# SPI_Encoders.net
KiCad netlist of a schematic drawn in Altium Designer
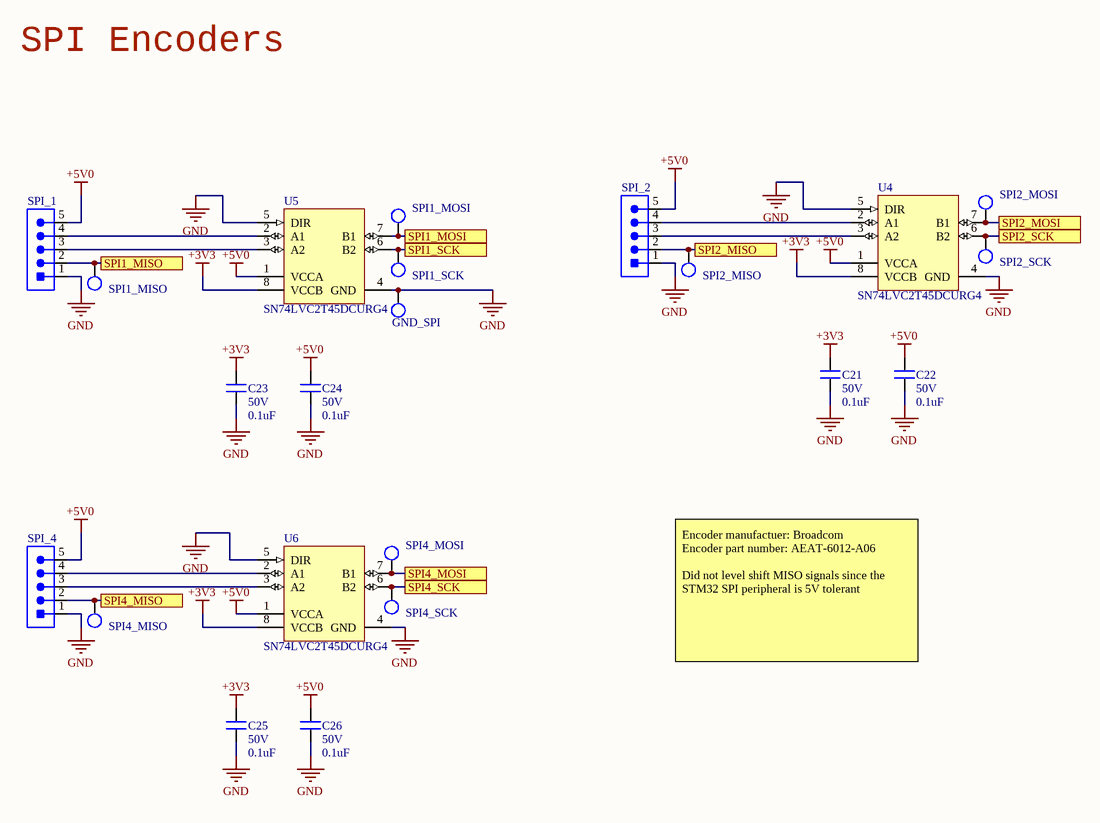
[diagram p0: SPI Encoders.SchDoc]

(export (version "E")
  (design (tool "Eeschema 10.0.6"))
  (components
    (comp (ref "C21")
      (value "0.1uF")
      (footprint "CAPC0603(1608)55_N")
      (description "CAP CER 0.1UF 50V X7R 0603")
      (fields
        (field (name "MPN") "CC0603KRX7R9BB104")
        (field (name "MANUFACTURER") "Yageo")
        (field (name "VOLTAGE RATING") "50V")
      )
      (libsource (lib "UWRT_Schematic_Library_2020") (part "CAP_0.1uF_50V_0603"))
    )
    (comp (ref "C22")
      (value "0.1uF")
      (footprint "CAPC0603(1608)55_N")
      (description "CAP CER 0.1UF 50V X7R 0603")
      (fields
        (field (name "MPN") "CC0603KRX7R9BB104")
        (field (name "MANUFACTURER") "Yageo")
        (field (name "VOLTAGE RATING") "50V")
      )
      (libsource (lib "UWRT_Schematic_Library_2020") (part "CAP_0.1uF_50V_0603"))
    )
    (comp (ref "C23")
      (value "0.1uF")
      (footprint "CAPC0603(1608)55_N")
      (description "CAP CER 0.1UF 50V X7R 0603")
      (fields
        (field (name "MPN") "CC0603KRX7R9BB104")
        (field (name "MANUFACTURER") "Yageo")
        (field (name "VOLTAGE RATING") "50V")
      )
      (libsource (lib "UWRT_Schematic_Library_2020") (part "CAP_0.1uF_50V_0603"))
    )
    (comp (ref "C24")
      (value "0.1uF")
      (footprint "CAPC0603(1608)55_N")
      (description "CAP CER 0.1UF 50V X7R 0603")
      (fields
        (field (name "MPN") "CC0603KRX7R9BB104")
        (field (name "MANUFACTURER") "Yageo")
        (field (name "VOLTAGE RATING") "50V")
      )
      (libsource (lib "UWRT_Schematic_Library_2020") (part "CAP_0.1uF_50V_0603"))
    )
    (comp (ref "C25")
      (value "0.1uF")
      (footprint "CAPC0603(1608)55_N")
      (description "CAP CER 0.1UF 50V X7R 0603")
      (fields
        (field (name "MPN") "CC0603KRX7R9BB104")
        (field (name "MANUFACTURER") "Yageo")
        (field (name "VOLTAGE RATING") "50V")
      )
      (libsource (lib "UWRT_Schematic_Library_2020") (part "CAP_0.1uF_50V_0603"))
    )
    (comp (ref "C26")
      (value "0.1uF")
      (footprint "CAPC0603(1608)55_N")
      (description "CAP CER 0.1UF 50V X7R 0603")
      (fields
        (field (name "MPN") "CC0603KRX7R9BB104")
        (field (name "MANUFACTURER") "Yageo")
        (field (name "VOLTAGE RATING") "50V")
      )
      (libsource (lib "UWRT_Schematic_Library_2020") (part "CAP_0.1uF_50V_0603"))
    )
    (comp (ref "GND_SPI")
      (value "TESTPOINT_LOOP")
      (footprint "TESTPOINT_LOOP")
      (description "Loop testpoint through-hole pad")
      (fields (field (name "MANUFACTURER") "Keystone Electronics"))
      (libsource (lib "UWRT_Schematic_Library_2020") (part "TESTPOINT_LOOP"))
    )
    (comp (ref "SPI1_MISO")
      (value "TESTPOINT_LOOP")
      (footprint "TESTPOINT_LOOP")
      (description "Loop testpoint through-hole pad")
      (fields (field (name "MANUFACTURER") "Keystone Electronics"))
      (libsource (lib "UWRT_Schematic_Library_2020") (part "TESTPOINT_LOOP"))
    )
    (comp (ref "SPI1_MOSI")
      (value "TESTPOINT_LOOP")
      (footprint "TESTPOINT_LOOP")
      (description "Loop testpoint through-hole pad")
      (fields (field (name "MANUFACTURER") "Keystone Electronics"))
      (libsource (lib "UWRT_Schematic_Library_2020") (part "TESTPOINT_LOOP"))
    )
    (comp (ref "SPI1_SCK")
      (value "TESTPOINT_LOOP")
      (footprint "TESTPOINT_LOOP")
      (description "Loop testpoint through-hole pad")
      (fields (field (name "MANUFACTURER") "Keystone Electronics"))
      (libsource (lib "UWRT_Schematic_Library_2020") (part "TESTPOINT_LOOP"))
    )
    (comp (ref "SPI2_MISO")
      (value "TESTPOINT_LOOP")
      (footprint "TESTPOINT_LOOP")
      (description "Loop testpoint through-hole pad")
      (fields (field (name "MANUFACTURER") "Keystone Electronics"))
      (libsource (lib "UWRT_Schematic_Library_2020") (part "TESTPOINT_LOOP"))
    )
    (comp (ref "SPI2_MOSI")
      (value "TESTPOINT_LOOP")
      (footprint "TESTPOINT_LOOP")
      (description "Loop testpoint through-hole pad")
      (fields (field (name "MANUFACTURER") "Keystone Electronics"))
      (libsource (lib "UWRT_Schematic_Library_2020") (part "TESTPOINT_LOOP"))
    )
    (comp (ref "SPI2_SCK")
      (value "TESTPOINT_LOOP")
      (footprint "TESTPOINT_LOOP")
      (description "Loop testpoint through-hole pad")
      (fields (field (name "MANUFACTURER") "Keystone Electronics"))
      (libsource (lib "UWRT_Schematic_Library_2020") (part "TESTPOINT_LOOP"))
    )
    (comp (ref "SPI4_MISO")
      (value "TESTPOINT_LOOP")
      (footprint "TESTPOINT_LOOP")
      (description "Loop testpoint through-hole pad")
      (fields (field (name "MANUFACTURER") "Keystone Electronics"))
      (libsource (lib "UWRT_Schematic_Library_2020") (part "TESTPOINT_LOOP"))
    )
    (comp (ref "SPI4_MOSI")
      (value "TESTPOINT_LOOP")
      (footprint "TESTPOINT_LOOP")
      (description "Loop testpoint through-hole pad")
      (fields (field (name "MANUFACTURER") "Keystone Electronics"))
      (libsource (lib "UWRT_Schematic_Library_2020") (part "TESTPOINT_LOOP"))
    )
    (comp (ref "SPI4_SCK")
      (value "TESTPOINT_LOOP")
      (footprint "TESTPOINT_LOOP")
      (description "Loop testpoint through-hole pad")
      (fields (field (name "MANUFACTURER") "Keystone Electronics"))
      (libsource (lib "UWRT_Schematic_Library_2020") (part "TESTPOINT_LOOP"))
    )
    (comp (ref "SPI_1")
      (value "CON_5M_SM4")
      (footprint "JST-B5B-SM4-TB")
      (description "CONN HEADER SMD 5POS 2MM")
      (fields
        (field (name "MANUFACTURER") "JST")
        (field (name "MANUFACTURER PART NUMBER") "B5B-PH-SM4-TB(LF)(SN)")
      )
      (libsource (lib "UWRT_Schematic_Library_2020") (part "CON_5M_SM4"))
    )
    (comp (ref "SPI_2")
      (value "CON_5M_SM4")
      (footprint "JST-B5B-SM4-TB")
      (description "CONN HEADER SMD 5POS 2MM")
      (fields
        (field (name "MANUFACTURER") "JST")
        (field (name "MANUFACTURER PART NUMBER") "B5B-PH-SM4-TB(LF)(SN)")
      )
      (libsource (lib "UWRT_Schematic_Library_2020") (part "CON_5M_SM4"))
    )
    (comp (ref "SPI_4")
      (value "CON_5M_SM4")
      (footprint "JST-B5B-SM4-TB")
      (description "CONN HEADER SMD 5POS 2MM")
      (fields
        (field (name "MANUFACTURER") "JST")
        (field (name "MANUFACTURER PART NUMBER") "B5B-PH-SM4-TB(LF)(SN)")
      )
      (libsource (lib "UWRT_Schematic_Library_2020") (part "CON_5M_SM4"))
    )
    (comp (ref "U4")
      (value "SN74LVC2T45DCURG4")
      (footprint "DCU0008A_N")
      (fields
        (field (name "MANUFACTURER") "Texas Instruments")
        (field (name "GENERIC PART NUMBER") "SN74LVC2T45")
      )
      (libsource (lib "Altium Content Vault") (part "TI-SN74XVC2T45-8"))
    )
    (comp (ref "U5")
      (value "SN74LVC2T45DCURG4")
      (footprint "DCU0008A_N")
      (fields
        (field (name "MANUFACTURER") "Texas Instruments")
        (field (name "GENERIC PART NUMBER") "SN74LVC2T45")
      )
      (libsource (lib "Altium Content Vault") (part "TI-SN74XVC2T45-8"))
    )
    (comp (ref "U6")
      (value "SN74LVC2T45DCURG4")
      (footprint "DCU0008A_N")
      (fields
        (field (name "MANUFACTURER") "Texas Instruments")
        (field (name "GENERIC PART NUMBER") "SN74LVC2T45")
      )
      (libsource (lib "Altium Content Vault") (part "TI-SN74XVC2T45-8"))
    )
  )
  (nets
    (net (code "1") (name "+3V3") (class "Default")
      (node (ref "C21") (pin "2") (pinfunction "2_2") (pintype "passive"))
      (node (ref "C23") (pin "2") (pinfunction "2_2") (pintype "passive"))
      (node (ref "C25") (pin "2") (pinfunction "2_2") (pintype "passive"))
      (node (ref "U4") (pin "8") (pinfunction "VCCB_8") (pintype "power_in"))
      (node (ref "U5") (pin "8") (pinfunction "VCCB_8") (pintype "power_in"))
      (node (ref "U6") (pin "8") (pinfunction "VCCB_8") (pintype "power_in"))
    )
    (net (code "2") (name "+5V0") (class "Default")
      (node (ref "C22") (pin "2") (pinfunction "2_2") (pintype "passive"))
      (node (ref "C24") (pin "2") (pinfunction "2_2") (pintype "passive"))
      (node (ref "C26") (pin "2") (pinfunction "2_2") (pintype "passive"))
      (node (ref "SPI_1") (pin "5") (pinfunction "5_5") (pintype "passive"))
      (node (ref "SPI_2") (pin "5") (pinfunction "5_5") (pintype "passive"))
      (node (ref "SPI_4") (pin "5") (pinfunction "5_5") (pintype "passive"))
      (node (ref "U4") (pin "1") (pinfunction "VCCA_1") (pintype "power_in"))
      (node (ref "U5") (pin "1") (pinfunction "VCCA_1") (pintype "power_in"))
      (node (ref "U6") (pin "1") (pinfunction "VCCA_1") (pintype "power_in"))
    )
    (net (code "3") (name "/SPI1_MISO") (class "Default")
      (node (ref "SPI1_MISO") (pin "1") (pintype "passive"))
      (node (ref "SPI_1") (pin "2") (pinfunction "2_2") (pintype "passive"))
    )
    (net (code "4") (name "/SPI1_MOSI") (class "Default")
      (node (ref "SPI1_MOSI") (pin "1") (pintype "passive"))
      (node (ref "U5") (pin "7") (pinfunction "B1_7") (pintype "bidirectional"))
    )
    (net (code "5") (name "/SPI1_SCK") (class "Default")
      (node (ref "SPI1_SCK") (pin "1") (pintype "passive"))
      (node (ref "U5") (pin "6") (pinfunction "B2_6") (pintype "bidirectional"))
    )
    (net (code "6") (name "/SPI2_MISO") (class "Default")
      (node (ref "SPI2_MISO") (pin "1") (pintype "passive"))
      (node (ref "SPI_2") (pin "2") (pinfunction "2_2") (pintype "passive"))
    )
    (net (code "7") (name "/SPI2_MOSI") (class "Default")
      (node (ref "SPI2_MOSI") (pin "1") (pintype "passive"))
      (node (ref "U4") (pin "7") (pinfunction "B1_7") (pintype "bidirectional"))
    )
    (net (code "8") (name "/SPI2_SCK") (class "Default")
      (node (ref "SPI2_SCK") (pin "1") (pintype "passive"))
      (node (ref "U4") (pin "6") (pinfunction "B2_6") (pintype "bidirectional"))
    )
    (net (code "9") (name "/SPI4_MISO") (class "Default")
      (node (ref "SPI4_MISO") (pin "1") (pintype "passive"))
      (node (ref "SPI_4") (pin "2") (pinfunction "2_2") (pintype "passive"))
    )
    (net (code "10") (name "/SPI4_MOSI") (class "Default")
      (node (ref "SPI4_MOSI") (pin "1") (pintype "passive"))
      (node (ref "U6") (pin "7") (pinfunction "B1_7") (pintype "bidirectional"))
    )
    (net (code "11") (name "/SPI4_SCK") (class "Default")
      (node (ref "SPI4_SCK") (pin "1") (pintype "passive"))
      (node (ref "U6") (pin "6") (pinfunction "B2_6") (pintype "bidirectional"))
    )
    (net (code "12") (name "GND") (class "Default")
      (node (ref "C21") (pin "1") (pinfunction "1_1") (pintype "passive"))
      (node (ref "C22") (pin "1") (pinfunction "1_1") (pintype "passive"))
      (node (ref "C23") (pin "1") (pinfunction "1_1") (pintype "passive"))
      (node (ref "C24") (pin "1") (pinfunction "1_1") (pintype "passive"))
      (node (ref "C25") (pin "1") (pinfunction "1_1") (pintype "passive"))
      (node (ref "C26") (pin "1") (pinfunction "1_1") (pintype "passive"))
      (node (ref "GND_SPI") (pin "1") (pintype "passive"))
      (node (ref "SPI_1") (pin "1") (pinfunction "1_1") (pintype "passive"))
      (node (ref "SPI_2") (pin "1") (pinfunction "1_1") (pintype "passive"))
      (node (ref "SPI_4") (pin "1") (pinfunction "1_1") (pintype "passive"))
      (node (ref "U4") (pin "4") (pinfunction "GND_4") (pintype "power_in"))
      (node (ref "U4") (pin "5") (pinfunction "DIR_5") (pintype "input"))
      (node (ref "U5") (pin "4") (pinfunction "GND_4") (pintype "power_in"))
      (node (ref "U5") (pin "5") (pinfunction "DIR_5") (pintype "input"))
      (node (ref "U6") (pin "4") (pinfunction "GND_4") (pintype "power_in"))
      (node (ref "U6") (pin "5") (pinfunction "DIR_5") (pintype "input"))
    )
    (net (code "13") (name "Net-(U4-A1)") (class "Default")
      (node (ref "SPI_2") (pin "4") (pinfunction "4_4") (pintype "passive"))
      (node (ref "U4") (pin "2") (pinfunction "A1_2") (pintype "bidirectional"))
    )
    (net (code "14") (name "Net-(U4-A2)") (class "Default")
      (node (ref "SPI_2") (pin "3") (pinfunction "3_3") (pintype "passive"))
      (node (ref "U4") (pin "3") (pinfunction "A2_3") (pintype "bidirectional"))
    )
    (net (code "15") (name "Net-(U5-A1)") (class "Default")
      (node (ref "SPI_1") (pin "4") (pinfunction "4_4") (pintype "passive"))
      (node (ref "U5") (pin "2") (pinfunction "A1_2") (pintype "bidirectional"))
    )
    (net (code "16") (name "Net-(U5-A2)") (class "Default")
      (node (ref "SPI_1") (pin "3") (pinfunction "3_3") (pintype "passive"))
      (node (ref "U5") (pin "3") (pinfunction "A2_3") (pintype "bidirectional"))
    )
    (net (code "17") (name "Net-(U6-A1)") (class "Default")
      (node (ref "SPI_4") (pin "4") (pinfunction "4_4") (pintype "passive"))
      (node (ref "U6") (pin "2") (pinfunction "A1_2") (pintype "bidirectional"))
    )
    (net (code "18") (name "Net-(U6-A2)") (class "Default")
      (node (ref "SPI_4") (pin "3") (pinfunction "3_3") (pintype "passive"))
      (node (ref "U6") (pin "3") (pinfunction "A2_3") (pintype "bidirectional"))
    )
  )
)
